# fonte1.net
KiCad netlist of a schematic drawn in EAGLE
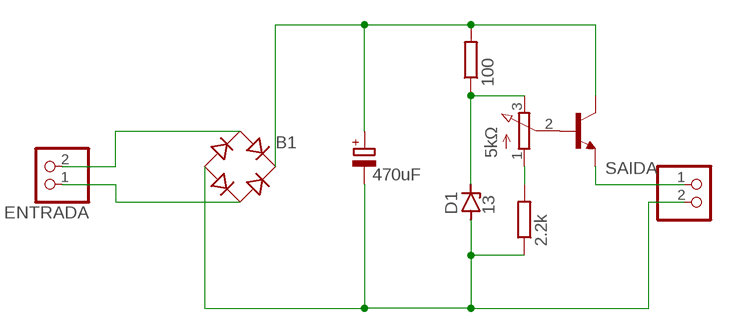
[diagram p0: schematic, sheet 1]

(export (version "E")
  (design (tool "Eeschema 10.0.6"))
  (components
    (comp (ref "B1")
      (value "RB1A")
      (footprint "eagle-import:RB1A")
      (libsource (lib "eagle-import") (part "RB1A"))
    )
    (comp (ref "C1")
      (value "470uF")
      (footprint "eagle-import:E2,5-6E")
      (libsource (lib "eagle-import") (part "CPOL-EUE2,5-6E"))
    )
    (comp (ref "D1")
      (value "13")
      (footprint "eagle-import:DO41Z10")
      (libsource (lib "eagle-import") (part "ZENER-DIODEDO41Z10"))
    )
    (comp (ref "ENTRADA")
      (value "PINHD-1X2")
      (footprint "eagle-import:1X02")
      (libsource (lib "eagle-import") (part "PINHD-1X2"))
    )
    (comp (ref "R2")
      (value "5kΩ")
      (footprint "eagle-import:3RP_1610N")
      (libsource (lib "eagle-import") (part "3RP/1610N"))
    )
    (comp (ref "R3")
      (value "2.2k")
      (footprint "eagle-import:0207_10")
      (libsource (lib "eagle-import") (part "R-EU_0207/10"))
    )
    (comp (ref "R4")
      (value "100")
      (footprint "eagle-import:0207_10")
      (libsource (lib "eagle-import") (part "R-EU_0207/10"))
    )
    (comp (ref "SAIDA")
      (value "PINHD-1X2")
      (footprint "eagle-import:1X02")
      (libsource (lib "eagle-import") (part "PINHD-1X2"))
    )
    (comp (ref "T1")
      (value "2N706")
      (footprint "eagle-import:TO18")
      (libsource (lib "eagle-import") (part "2N706"))
    )
  )
  (nets
    (net (code "1") (name "Net-(B1-Pad-)") (class "Default")
      (node (ref "B1") (pin "-") (pinfunction "-_-") (pintype "passive"))
      (node (ref "C1") (pin "-") (pinfunction "-_-") (pintype "passive"))
      (node (ref "D1") (pin "A") (pinfunction "A_A") (pintype "passive"))
      (node (ref "R3") (pin "1") (pinfunction "1_1") (pintype "passive"))
      (node (ref "SAIDA") (pin "2") (pinfunction "2_2") (pintype "passive"))
    )
    (net (code "2") (name "Net-(B1-PadAC1)") (class "Default")
      (node (ref "B1") (pin "AC1") (pinfunction "AC1_AC1") (pintype "passive"))
      (node (ref "ENTRADA") (pin "2") (pinfunction "2_2") (pintype "passive"))
    )
    (net (code "3") (name "Net-(B1-PadAC2)") (class "Default")
      (node (ref "B1") (pin "AC2") (pinfunction "AC2_AC2") (pintype "passive"))
      (node (ref "ENTRADA") (pin "1") (pinfunction "1_1") (pintype "passive"))
    )
    (net (code "4") (name "Net-(R2-A)") (class "Default")
      (node (ref "R2") (pin "1") (pinfunction "A_1") (pintype "passive"))
      (node (ref "R3") (pin "2") (pinfunction "2_2") (pintype "passive"))
    )
    (net (code "5") (name "Net-(R2-E)") (class "Default")
      (node (ref "D1") (pin "C") (pinfunction "C_C") (pintype "passive"))
      (node (ref "R2") (pin "3") (pinfunction "E_3") (pintype "passive"))
      (node (ref "R4") (pin "1") (pinfunction "1_1") (pintype "passive"))
    )
    (net (code "6") (name "Net-(R2-S)") (class "Default")
      (node (ref "R2") (pin "2") (pinfunction "S_2") (pintype "passive"))
      (node (ref "T1") (pin "2") (pinfunction "B_2") (pintype "passive"))
    )
    (net (code "7") (name "Net-(T1-C)") (class "Default")
      (node (ref "B1") (pin "+") (pinfunction "+_+") (pintype "passive"))
      (node (ref "C1") (pin "+") (pinfunction "+_+") (pintype "passive"))
      (node (ref "R4") (pin "2") (pinfunction "2_2") (pintype "passive"))
      (node (ref "T1") (pin "3") (pinfunction "C_3") (pintype "passive"))
    )
    (net (code "8") (name "Net-(T1-E)") (class "Default")
      (node (ref "SAIDA") (pin "1") (pinfunction "1_1") (pintype "passive"))
      (node (ref "T1") (pin "1") (pinfunction "E_1") (pintype "passive"))
    )
  )
)
